# uMultimeter_MCU_Sch.net
KiCad netlist of a schematic drawn in Altium Designer
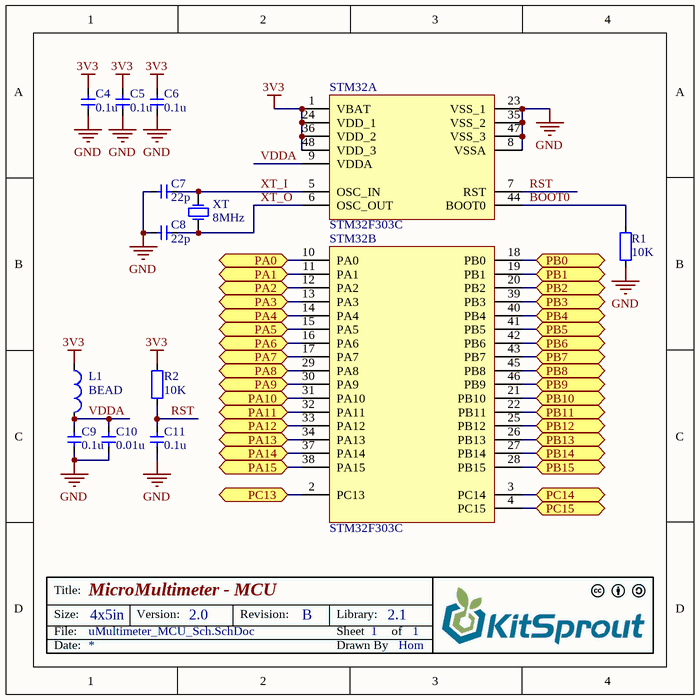
[diagram p0: uMultimeter_MCU_Sch.SchDoc]

(export (version "E")
  (design (tool "Eeschema 10.0.6"))
  (components
    (comp (ref "C4")
      (value "0.1u")
      (footprint "PCB_PassiveCap:CAP_0603")
      (description "Capacitor")
      (fields (field (name "Comment") "Cap_0603"))
      (libsource (lib "SCH_Passive") (part "Cap_0603"))
    )
    (comp (ref "C5")
      (value "0.1u")
      (footprint "PCB_PassiveCap:CAP_0603")
      (description "Capacitor")
      (fields (field (name "Comment") "Cap_0603"))
      (libsource (lib "SCH_Passive") (part "Cap_0603"))
    )
    (comp (ref "C6")
      (value "0.1u")
      (footprint "PCB_PassiveCap:CAP_0603")
      (description "Capacitor")
      (fields (field (name "Comment") "Cap_0603"))
      (libsource (lib "SCH_Passive") (part "Cap_0603"))
    )
    (comp (ref "C7")
      (value "22p")
      (footprint "PCB_PassiveCap:CAP_0603")
      (description "Capacitor")
      (fields (field (name "Comment") "Cap_0603"))
      (libsource (lib "SCH_Passive") (part "Cap_0603"))
    )
    (comp (ref "C8")
      (value "22p")
      (footprint "PCB_PassiveCap:CAP_0603")
      (description "Capacitor")
      (fields (field (name "Comment") "Cap_0603"))
      (libsource (lib "SCH_Passive") (part "Cap_0603"))
    )
    (comp (ref "C9")
      (value "0.1u")
      (footprint "PCB_PassiveCap:CAP_0603")
      (description "Capacitor")
      (fields (field (name "Comment") "Cap_0603"))
      (libsource (lib "SCH_Passive") (part "Cap_0603"))
    )
    (comp (ref "C10")
      (value "0.01u")
      (footprint "PCB_PassiveCap:CAP_0603")
      (description "Capacitor")
      (fields (field (name "Comment") "Cap_0603"))
      (libsource (lib "SCH_Passive") (part "Cap_0603"))
    )
    (comp (ref "C11")
      (value "0.1u")
      (footprint "PCB_PassiveCap:CAP_0603")
      (description "Capacitor")
      (fields (field (name "Comment") "Cap_0603"))
      (libsource (lib "SCH_Passive") (part "Cap_0603"))
    )
    (comp (ref "L1")
      (value "BEAD")
      (footprint "PCB_PassiveInd:IND_0603")
      (description "Inductor")
      (fields (field (name "Comment") "Ind_0603"))
      (libsource (lib "SCH_Passive") (part "Ind_0603"))
    )
    (comp (ref "R1")
      (value "10K")
      (footprint "PCB_PassiveRes:RES_0603")
      (description "Resistor")
      (fields (field (name "Comment") "Res_0603"))
      (libsource (lib "SCH_Passive") (part "Res_0603"))
    )
    (comp (ref "R2")
      (value "10K")
      (footprint "PCB_PassiveRes:RES_0603")
      (description "Resistor")
      (fields (field (name "Comment") "Res_0603"))
      (libsource (lib "SCH_Passive") (part "Res_0603"))
    )
    (comp (ref "STM32")
      (value "STM32F303C")
      (footprint "PCB_IntegratedCircuit:LQFP_P0.5_48")
      (description "MCU")
      (libsource (lib "SCH_IntegratedCircuit") (part "STM32F303C"))
    )
    (comp (ref "XT")
      (value "8MHz")
      (footprint "PCB_Oscillator:XT_5032_2")
      (description "Crystal Oscillator")
      (fields (field (name "Comment") "XTAL_5032_2P"))
      (libsource (lib "SCH_Oscillator") (part "XTAL_5032_2P"))
    )
  )
  (nets
    (net (code "1") (name "/BOOT0") (class "Default")
      (node (ref "R1") (pin "2") (pinfunction "2_2") (pintype "passive"))
      (node (ref "STM32") (pin "44") (pinfunction "BOOT0_44") (pintype "passive"))
    )
    (net (code "2") (name "/PA0") (class "Default")
      (node (ref "STM32") (pin "10") (pinfunction "PA0_10") (pintype "passive"))
    )
    (net (code "3") (name "/PA1") (class "Default")
      (node (ref "STM32") (pin "11") (pinfunction "PA1_11") (pintype "passive"))
    )
    (net (code "4") (name "/PA2") (class "Default")
      (node (ref "STM32") (pin "12") (pinfunction "PA2_12") (pintype "passive"))
    )
    (net (code "5") (name "/PA3") (class "Default")
      (node (ref "STM32") (pin "13") (pinfunction "PA3_13") (pintype "passive"))
    )
    (net (code "6") (name "/PA4") (class "Default")
      (node (ref "STM32") (pin "14") (pinfunction "PA4_14") (pintype "passive"))
    )
    (net (code "7") (name "/PA5") (class "Default")
      (node (ref "STM32") (pin "15") (pinfunction "PA5_15") (pintype "passive"))
    )
    (net (code "8") (name "/PA6") (class "Default")
      (node (ref "STM32") (pin "16") (pinfunction "PA6_16") (pintype "passive"))
    )
    (net (code "9") (name "/PA7") (class "Default")
      (node (ref "STM32") (pin "17") (pinfunction "PA7_17") (pintype "passive"))
    )
    (net (code "10") (name "/PA8") (class "Default")
      (node (ref "STM32") (pin "29") (pinfunction "PA8_29") (pintype "passive"))
    )
    (net (code "11") (name "/PA9") (class "Default")
      (node (ref "STM32") (pin "30") (pinfunction "PA9_30") (pintype "passive"))
    )
    (net (code "12") (name "/PA10") (class "Default")
      (node (ref "STM32") (pin "31") (pinfunction "PA10_31") (pintype "passive"))
    )
    (net (code "13") (name "/PA11") (class "Default")
      (node (ref "STM32") (pin "32") (pinfunction "PA11_32") (pintype "passive"))
    )
    (net (code "14") (name "/PA12") (class "Default")
      (node (ref "STM32") (pin "33") (pinfunction "PA12_33") (pintype "passive"))
    )
    (net (code "15") (name "/PA13") (class "Default")
      (node (ref "STM32") (pin "34") (pinfunction "PA13_34") (pintype "passive"))
    )
    (net (code "16") (name "/PA14") (class "Default")
      (node (ref "STM32") (pin "37") (pinfunction "PA14_37") (pintype "passive"))
    )
    (net (code "17") (name "/PA15") (class "Default")
      (node (ref "STM32") (pin "38") (pinfunction "PA15_38") (pintype "passive"))
    )
    (net (code "18") (name "/PB0") (class "Default")
      (node (ref "STM32") (pin "18") (pinfunction "PB0_18") (pintype "passive"))
    )
    (net (code "19") (name "/PB1") (class "Default")
      (node (ref "STM32") (pin "19") (pinfunction "PB1_19") (pintype "passive"))
    )
    (net (code "20") (name "/PB2") (class "Default")
      (node (ref "STM32") (pin "20") (pinfunction "PB2_20") (pintype "passive"))
    )
    (net (code "21") (name "/PB3") (class "Default")
      (node (ref "STM32") (pin "39") (pinfunction "PB3_39") (pintype "passive"))
    )
    (net (code "22") (name "/PB4") (class "Default")
      (node (ref "STM32") (pin "40") (pinfunction "PB4_40") (pintype "passive"))
    )
    (net (code "23") (name "/PB5") (class "Default")
      (node (ref "STM32") (pin "41") (pinfunction "PB5_41") (pintype "passive"))
    )
    (net (code "24") (name "/PB6") (class "Default")
      (node (ref "STM32") (pin "42") (pinfunction "PB6_42") (pintype "passive"))
    )
    (net (code "25") (name "/PB7") (class "Default")
      (node (ref "STM32") (pin "43") (pinfunction "PB7_43") (pintype "passive"))
    )
    (net (code "26") (name "/PB8") (class "Default")
      (node (ref "STM32") (pin "45") (pinfunction "PB8_45") (pintype "passive"))
    )
    (net (code "27") (name "/PB9") (class "Default")
      (node (ref "STM32") (pin "46") (pinfunction "PB9_46") (pintype "passive"))
    )
    (net (code "28") (name "/PB10") (class "Default")
      (node (ref "STM32") (pin "21") (pinfunction "PB10_21") (pintype "passive"))
    )
    (net (code "29") (name "/PB11") (class "Default")
      (node (ref "STM32") (pin "22") (pinfunction "PB11_22") (pintype "passive"))
    )
    (net (code "30") (name "/PB12") (class "Default")
      (node (ref "STM32") (pin "25") (pinfunction "PB12_25") (pintype "passive"))
    )
    (net (code "31") (name "/PB13") (class "Default")
      (node (ref "STM32") (pin "26") (pinfunction "PB13_26") (pintype "passive"))
    )
    (net (code "32") (name "/PB14") (class "Default")
      (node (ref "STM32") (pin "27") (pinfunction "PB14_27") (pintype "passive"))
    )
    (net (code "33") (name "/PB15") (class "Default")
      (node (ref "STM32") (pin "28") (pinfunction "PB15_28") (pintype "passive"))
    )
    (net (code "34") (name "/PC13") (class "Default")
      (node (ref "STM32") (pin "2") (pinfunction "PC13_2") (pintype "passive"))
    )
    (net (code "35") (name "/PC14") (class "Default")
      (node (ref "STM32") (pin "3") (pinfunction "PC14_3") (pintype "passive"))
    )
    (net (code "36") (name "/PC15") (class "Default")
      (node (ref "STM32") (pin "4") (pinfunction "PC15_4") (pintype "passive"))
    )
    (net (code "37") (name "/RST") (class "Default")
      (node (ref "C11") (pin "2") (pinfunction "2_2") (pintype "passive"))
      (node (ref "R2") (pin "1") (pinfunction "1_1") (pintype "passive"))
      (node (ref "STM32") (pin "7") (pinfunction "RST_7") (pintype "passive"))
    )
    (net (code "38") (name "/VDDA") (class "Default")
      (node (ref "C10") (pin "2") (pinfunction "2_2") (pintype "passive"))
      (node (ref "C9") (pin "2") (pinfunction "2_2") (pintype "passive"))
      (node (ref "L1") (pin "2") (pinfunction "2_2") (pintype "passive"))
      (node (ref "STM32") (pin "9") (pinfunction "VDDA_9") (pintype "passive"))
    )
    (net (code "39") (name "/XT_I") (class "Default")
      (node (ref "C7") (pin "1") (pinfunction "1_1") (pintype "passive"))
      (node (ref "STM32") (pin "5") (pinfunction "OSC_IN_5") (pintype "passive"))
      (node (ref "XT") (pin "2") (pinfunction "OSC2_2") (pintype "passive"))
    )
    (net (code "40") (name "/XT_O") (class "Default")
      (node (ref "C8") (pin "1") (pinfunction "1_1") (pintype "passive"))
      (node (ref "STM32") (pin "6") (pinfunction "OSC_OUT_6") (pintype "passive"))
      (node (ref "XT") (pin "1") (pinfunction "OSC1_1") (pintype "passive"))
    )
    (net (code "41") (name "3V3") (class "Default")
      (node (ref "C4") (pin "2") (pinfunction "2_2") (pintype "passive"))
      (node (ref "C5") (pin "2") (pinfunction "2_2") (pintype "passive"))
      (node (ref "C6") (pin "2") (pinfunction "2_2") (pintype "passive"))
      (node (ref "L1") (pin "1") (pinfunction "1_1") (pintype "passive"))
      (node (ref "R2") (pin "2") (pinfunction "2_2") (pintype "passive"))
      (node (ref "STM32") (pin "1") (pinfunction "VBAT_1") (pintype "passive"))
      (node (ref "STM32") (pin "24") (pinfunction "VDD_1_24") (pintype "passive"))
      (node (ref "STM32") (pin "36") (pinfunction "VDD_2_36") (pintype "passive"))
      (node (ref "STM32") (pin "48") (pinfunction "VDD_3_48") (pintype "passive"))
    )
    (net (code "42") (name "GND") (class "Default")
      (node (ref "C10") (pin "1") (pinfunction "1_1") (pintype "passive"))
      (node (ref "C11") (pin "1") (pinfunction "1_1") (pintype "passive"))
      (node (ref "C4") (pin "1") (pinfunction "1_1") (pintype "passive"))
      (node (ref "C5") (pin "1") (pinfunction "1_1") (pintype "passive"))
      (node (ref "C6") (pin "1") (pinfunction "1_1") (pintype "passive"))
      (node (ref "C7") (pin "2") (pinfunction "2_2") (pintype "passive"))
      (node (ref "C8") (pin "2") (pinfunction "2_2") (pintype "passive"))
      (node (ref "C9") (pin "1") (pinfunction "1_1") (pintype "passive"))
      (node (ref "R1") (pin "1") (pinfunction "1_1") (pintype "passive"))
      (node (ref "STM32") (pin "23") (pinfunction "VSS_1_23") (pintype "passive"))
      (node (ref "STM32") (pin "35") (pinfunction "VSS_2_35") (pintype "passive"))
      (node (ref "STM32") (pin "47") (pinfunction "VSS_3_47") (pintype "passive"))
      (node (ref "STM32") (pin "8") (pinfunction "VSSA_8") (pintype "passive"))
    )
  )
)
